# pcb.net
KiCad netlist of a schematic drawn in EAGLE
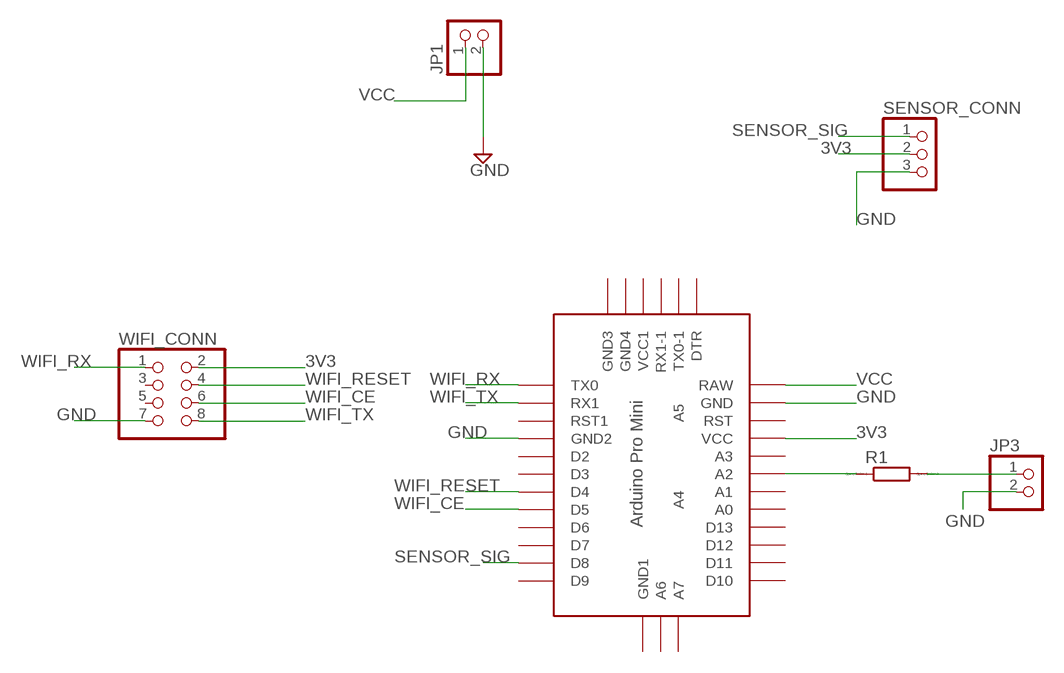
[diagram p0: schematic, sheet 1]

(export (version "E")
  (design (tool "Eeschema 10.0.6"))
  (components
    (comp (ref "JP1")
      (value "PINHD-1X2")
      (footprint "eagle-import:1X02")
      (libsource (lib "eagle-import") (part "PINHD-1X2"))
    )
    (comp (ref "JP3")
      (value "PINHD-1X2")
      (footprint "eagle-import:1X02")
      (libsource (lib "eagle-import") (part "PINHD-1X2"))
    )
    (comp (ref "R1")
      (value "R0207/10")
      (footprint "eagle-import:0207_10")
      (libsource (lib "eagle-import") (part "R0207/10"))
    )
    (comp (ref "SENSOR_CONN")
      (value "PINHD-1X3")
      (footprint "eagle-import:1X03")
      (libsource (lib "eagle-import") (part "PINHD-1X3"))
    )
    (comp (ref "U$1")
      (value "ABK-PRO-MINI")
      (footprint "eagle-import:ABK-PRO-MINI")
      (libsource (lib "eagle-import") (part "ABK-PRO-MINI"))
    )
    (comp (ref "WIFI_CONN")
      (value "PINHD-2X4")
      (footprint "eagle-import:2X04")
      (libsource (lib "eagle-import") (part "PINHD-2X4"))
    )
  )
  (nets
    (net (code "1") (name "/3V3") (class "Default")
      (node (ref "SENSOR_CONN") (pin "2") (pinfunction "2_2") (pintype "passive"))
      (node (ref "U$1") (pin "VCC") (pinfunction "VCC_VCC") (pintype "bidirectional"))
      (node (ref "WIFI_CONN") (pin "2") (pinfunction "2_2") (pintype "passive"))
    )
    (net (code "2") (name "/SENSOR_SIG") (class "Default")
      (node (ref "SENSOR_CONN") (pin "1") (pinfunction "1_1") (pintype "passive"))
      (node (ref "U$1") (pin "D8") (pinfunction "D8_D8") (pintype "bidirectional"))
    )
    (net (code "3") (name "/VCC") (class "Default")
      (node (ref "JP1") (pin "1") (pinfunction "1_1") (pintype "passive"))
      (node (ref "U$1") (pin "RAW") (pinfunction "RAW_RAW") (pintype "bidirectional"))
    )
    (net (code "4") (name "/WIFI_CE") (class "Default")
      (node (ref "U$1") (pin "D5") (pinfunction "D5_D5") (pintype "bidirectional"))
      (node (ref "WIFI_CONN") (pin "6") (pinfunction "6_6") (pintype "passive"))
    )
    (net (code "5") (name "/WIFI_RESET") (class "Default")
      (node (ref "U$1") (pin "D4") (pinfunction "D4_D4") (pintype "bidirectional"))
      (node (ref "WIFI_CONN") (pin "4") (pinfunction "4_4") (pintype "passive"))
    )
    (net (code "6") (name "/WIFI_RX") (class "Default")
      (node (ref "U$1") (pin "TX0") (pinfunction "TX0_TX0") (pintype "bidirectional"))
      (node (ref "WIFI_CONN") (pin "1") (pinfunction "1_1") (pintype "passive"))
    )
    (net (code "7") (name "/WIFI_TX") (class "Default")
      (node (ref "U$1") (pin "RX1") (pinfunction "RX1_RX1") (pintype "bidirectional"))
      (node (ref "WIFI_CONN") (pin "8") (pinfunction "8_8") (pintype "passive"))
    )
    (net (code "8") (name "GND") (class "Default")
      (node (ref "JP1") (pin "2") (pinfunction "2_2") (pintype "passive"))
      (node (ref "JP3") (pin "2") (pinfunction "2_2") (pintype "passive"))
      (node (ref "SENSOR_CONN") (pin "3") (pinfunction "3_3") (pintype "passive"))
      (node (ref "U$1") (pin "GND") (pinfunction "GND_GND") (pintype "bidirectional"))
      (node (ref "U$1") (pin "GND1") (pinfunction "GND2_GND1") (pintype "bidirectional"))
      (node (ref "WIFI_CONN") (pin "7") (pinfunction "7_7") (pintype "passive"))
    )
    (net (code "9") (name "Net-(JP3-Pad1)") (class "Default")
      (node (ref "JP3") (pin "1") (pinfunction "1_1") (pintype "passive"))
      (node (ref "R1") (pin "2") (pinfunction "2_2") (pintype "passive"))
    )
    (net (code "10") (name "Net-(R1-Pad1)") (class "Default")
      (node (ref "R1") (pin "1") (pinfunction "1_1") (pintype "passive"))
      (node (ref "U$1") (pin "A2") (pinfunction "A2_A2") (pintype "bidirectional"))
    )
    (net (code "11") (name "unconnected-(U$1-GND1-PadGND4)") (class "Default")
      (node (ref "U$1") (pin "GND4") (pinfunction "GND1_GND4") (pintype "bidirectional"))
    )
    (net (code "12") (name "unconnected-(U$1-GND3-PadGND2)") (class "Default")
      (node (ref "U$1") (pin "GND2") (pinfunction "GND3_GND2") (pintype "bidirectional"))
    )
    (net (code "13") (name "unconnected-(U$1-GND4-PadGND3)") (class "Default")
      (node (ref "U$1") (pin "GND3") (pinfunction "GND4_GND3") (pintype "bidirectional"))
    )
    (net (code "14") (name "unconnected-(U$1-PadA0)") (class "Default")
      (node (ref "U$1") (pin "A0") (pinfunction "A0_A0") (pintype "bidirectional"))
    )
    (net (code "15") (name "unconnected-(U$1-PadA1)") (class "Default")
      (node (ref "U$1") (pin "A1") (pinfunction "A1_A1") (pintype "bidirectional"))
    )
    (net (code "16") (name "unconnected-(U$1-PadA3)") (class "Default")
      (node (ref "U$1") (pin "A3") (pinfunction "A3_A3") (pintype "bidirectional"))
    )
    (net (code "17") (name "unconnected-(U$1-PadA4)") (class "Default")
      (node (ref "U$1") (pin "A4") (pinfunction "A4_A4") (pintype "bidirectional"))
    )
    (net (code "18") (name "unconnected-(U$1-PadA5)") (class "Default")
      (node (ref "U$1") (pin "A5") (pinfunction "A5_A5") (pintype "bidirectional"))
    )
    (net (code "19") (name "unconnected-(U$1-PadA6)") (class "Default")
      (node (ref "U$1") (pin "A6") (pinfunction "A6_A6") (pintype "bidirectional"))
    )
    (net (code "20") (name "unconnected-(U$1-PadA7)") (class "Default")
      (node (ref "U$1") (pin "A7") (pinfunction "A7_A7") (pintype "bidirectional"))
    )
    (net (code "21") (name "unconnected-(U$1-PadD2)") (class "Default")
      (node (ref "U$1") (pin "D2") (pinfunction "D2_D2") (pintype "bidirectional"))
    )
    (net (code "22") (name "unconnected-(U$1-PadD3)") (class "Default")
      (node (ref "U$1") (pin "D3") (pinfunction "D3_D3") (pintype "bidirectional"))
    )
    (net (code "23") (name "unconnected-(U$1-PadD6)") (class "Default")
      (node (ref "U$1") (pin "D6") (pinfunction "D6_D6") (pintype "bidirectional"))
    )
    (net (code "24") (name "unconnected-(U$1-PadD7)") (class "Default")
      (node (ref "U$1") (pin "D7") (pinfunction "D7_D7") (pintype "bidirectional"))
    )
    (net (code "25") (name "unconnected-(U$1-PadD9)") (class "Default")
      (node (ref "U$1") (pin "D9") (pinfunction "D9_D9") (pintype "bidirectional"))
    )
    (net (code "26") (name "unconnected-(U$1-PadD10)") (class "Default")
      (node (ref "U$1") (pin "D10") (pinfunction "D10_D10") (pintype "bidirectional"))
    )
    (net (code "27") (name "unconnected-(U$1-PadD11)") (class "Default")
      (node (ref "U$1") (pin "D11") (pinfunction "D11_D11") (pintype "bidirectional"))
    )
    (net (code "28") (name "unconnected-(U$1-PadD12)") (class "Default")
      (node (ref "U$1") (pin "D12") (pinfunction "D12_D12") (pintype "bidirectional"))
    )
    (net (code "29") (name "unconnected-(U$1-PadD13)") (class "Default")
      (node (ref "U$1") (pin "D13") (pinfunction "D13_D13") (pintype "bidirectional"))
    )
    (net (code "30") (name "unconnected-(U$1-PadDTR)") (class "Default")
      (node (ref "U$1") (pin "DTR") (pinfunction "DTR_DTR") (pintype "bidirectional"))
    )
    (net (code "31") (name "unconnected-(U$1-PadRST)") (class "Default")
      (node (ref "U$1") (pin "RST") (pinfunction "RST_RST") (pintype "bidirectional"))
    )
    (net (code "32") (name "unconnected-(U$1-PadRST1)") (class "Default")
      (node (ref "U$1") (pin "RST1") (pinfunction "RST1_RST1") (pintype "bidirectional"))
    )
    (net (code "33") (name "unconnected-(U$1-PadRX1-1)") (class "Default")
      (node (ref "U$1") (pin "RX1-1") (pinfunction "RX1-1_RX1-1") (pintype "bidirectional"))
    )
    (net (code "34") (name "unconnected-(U$1-PadTX0-1)") (class "Default")
      (node (ref "U$1") (pin "TX0-1") (pinfunction "TX0-1_TX0-1") (pintype "bidirectional"))
    )
    (net (code "35") (name "unconnected-(U$1-PadVCC1)") (class "Default")
      (node (ref "U$1") (pin "VCC1") (pinfunction "VCC1_VCC1") (pintype "bidirectional"))
    )
    (net (code "36") (name "unconnected-(WIFI_CONN-Pad3)") (class "Default")
      (node (ref "WIFI_CONN") (pin "3") (pinfunction "3_3") (pintype "passive"))
    )
    (net (code "37") (name "unconnected-(WIFI_CONN-Pad5)") (class "Default")
      (node (ref "WIFI_CONN") (pin "5") (pinfunction "5_5") (pintype "passive"))
    )
  )
)
